# Motor_shield_2_0.net
KiCad netlist of a schematic drawn in EAGLE
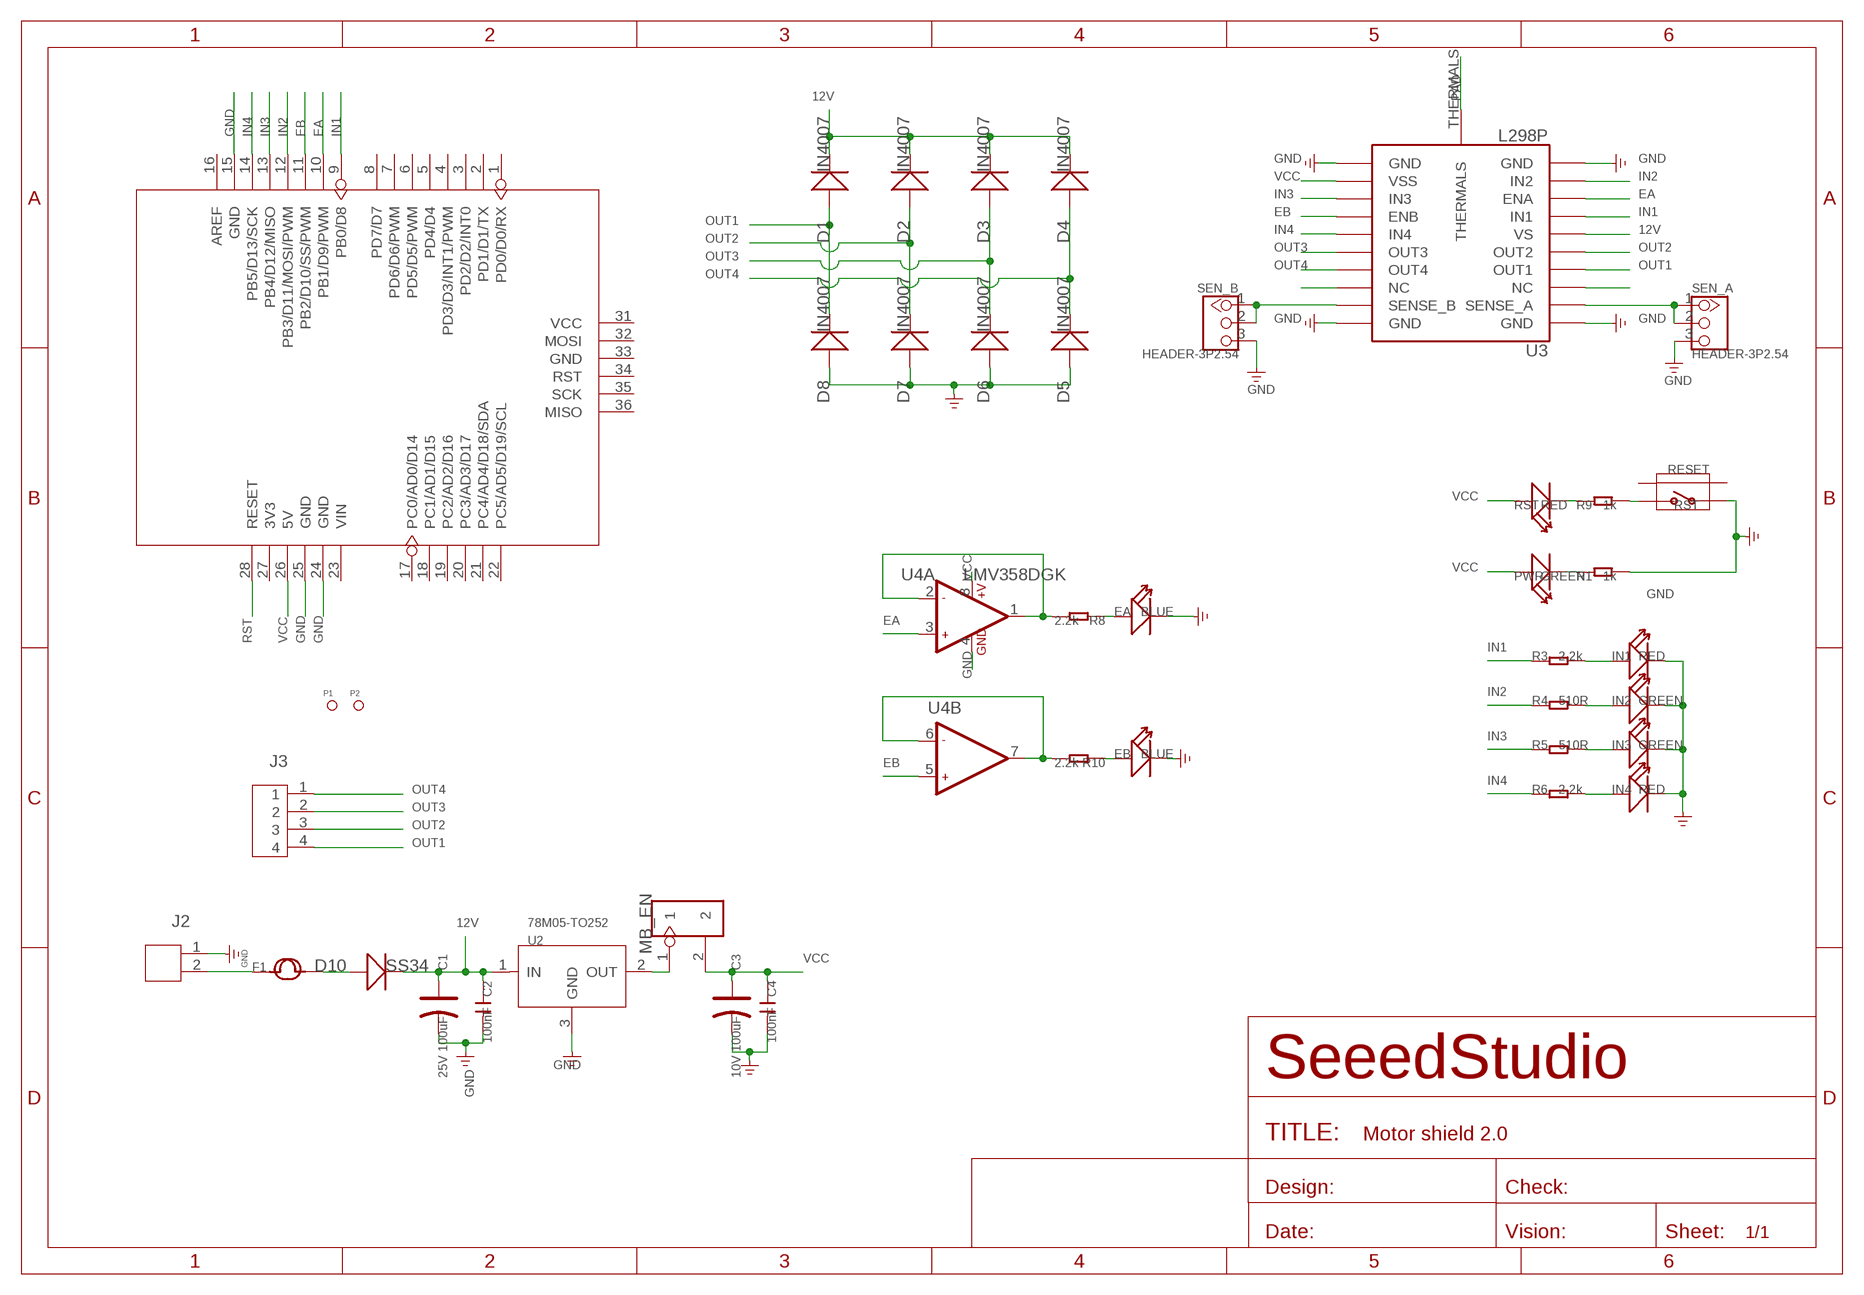
[diagram p0: schematic, sheet 1]

(export (version "E")
  (design (tool "Eeschema 10.0.6"))
  (components
    (comp (ref "C1")
      (value "25V 100uF")
      (footprint "eagle-import:ELECTRO-SMD-D-5.6MM")
      (libsource (lib "eagle-import") (part "CAP-ELECTRO-D"))
    )
    (comp (ref "C2")
      (value "100nF")
      (footprint "eagle-import:C0603")
      (libsource (lib "eagle-import") (part "C-0603"))
    )
    (comp (ref "C3")
      (value "10V 100uF")
      (footprint "eagle-import:AVX-B")
      (libsource (lib "eagle-import") (part "CAP-AVX-B"))
    )
    (comp (ref "C4")
      (value "100nF")
      (footprint "eagle-import:C0603")
      (libsource (lib "eagle-import") (part "C-0603"))
    )
    (comp (ref "D1")
      (value "IN4007")
      (footprint "eagle-import:D2010")
      (libsource (lib "eagle-import") (part "D'SMA'"))
    )
    (comp (ref "D2")
      (value "IN4007")
      (footprint "eagle-import:D2010")
      (libsource (lib "eagle-import") (part "D'SMA'"))
    )
    (comp (ref "D3")
      (value "IN4007")
      (footprint "eagle-import:D2010")
      (libsource (lib "eagle-import") (part "D'SMA'"))
    )
    (comp (ref "D4")
      (value "IN4007")
      (footprint "eagle-import:D2010")
      (libsource (lib "eagle-import") (part "D'SMA'"))
    )
    (comp (ref "D5")
      (value "IN4007")
      (footprint "eagle-import:D2010")
      (libsource (lib "eagle-import") (part "D'SMA'"))
    )
    (comp (ref "D6")
      (value "IN4007")
      (footprint "eagle-import:D2010")
      (libsource (lib "eagle-import") (part "D'SMA'"))
    )
    (comp (ref "D7")
      (value "IN4007")
      (footprint "eagle-import:D2010")
      (libsource (lib "eagle-import") (part "D'SMA'"))
    )
    (comp (ref "D8")
      (value "IN4007")
      (footprint "eagle-import:D2010")
      (libsource (lib "eagle-import") (part "D'SMA'"))
    )
    (comp (ref "D10")
      (value "SS34")
      (footprint "eagle-import:DO-214AB")
      (libsource (lib "eagle-import") (part "D'DO-214AB'"))
    )
    (comp (ref "EA")
      (value "BLUE")
      (footprint "eagle-import:D0603")
      (libsource (lib "eagle-import") (part "007-LED0603"))
    )
    (comp (ref "EB")
      (value "BLUE")
      (footprint "eagle-import:D0603")
      (libsource (lib "eagle-import") (part "007-LED0603"))
    )
    (comp (ref "F1")
      (value "FUSE'RLD30P250UF'")
      (footprint "eagle-import:0311")
      (libsource (lib "eagle-import") (part "FUSE'RLD30P250UF'"))
    )
    (comp (ref "IN1")
      (value "RED")
      (footprint "eagle-import:D0603")
      (libsource (lib "eagle-import") (part "007-LED0603"))
    )
    (comp (ref "IN2")
      (value "GREEN")
      (footprint "eagle-import:D0603")
      (libsource (lib "eagle-import") (part "007-LED0603"))
    )
    (comp (ref "IN3")
      (value "GREEN")
      (footprint "eagle-import:D0603")
      (libsource (lib "eagle-import") (part "007-LED0603"))
    )
    (comp (ref "IN4")
      (value "RED")
      (footprint "eagle-import:D0603")
      (libsource (lib "eagle-import") (part "007-LED0603"))
    )
    (comp (ref "J2")
      (value "JST-2P-LEADED'3.36'")
      (footprint "eagle-import:2P-3.36-LEADED-7X7")
      (libsource (lib "eagle-import") (part "JST-2P-LEADED'3.36'"))
    )
    (comp (ref "J3")
      (value "JST-4P-3.36-LEADED")
      (footprint "eagle-import:4P-3.36-LEADED-7X14")
      (libsource (lib "eagle-import") (part "JST-4P-3.36-LEADED"))
    )
    (comp (ref "MB_EN")
      (value "HEADER-2P-65/35MIL")
      (footprint "eagle-import:2P-2.54-65_35MIL")
      (libsource (lib "eagle-import") (part "HEADER-2P-65/35MIL"))
    )
    (comp (ref "P1")
      (value "PAD-MARK")
      (footprint "eagle-import:ROUND-MARK-1.0")
      (fields (field (name "PARTNO") "DNP"))
      (libsource (lib "eagle-import") (part "PAD-MARK"))
    )
    (comp (ref "P2")
      (value "PAD-MARK")
      (footprint "eagle-import:ROUND-MARK-1.0")
      (fields (field (name "PARTNO") "DNP"))
      (libsource (lib "eagle-import") (part "PAD-MARK"))
    )
    (comp (ref "PWR")
      (value "GREEN")
      (footprint "eagle-import:D0603")
      (libsource (lib "eagle-import") (part "007-LED0603"))
    )
    (comp (ref "R1")
      (value "1k")
      (footprint "eagle-import:R0603")
      (libsource (lib "eagle-import") (part "R-0603"))
    )
    (comp (ref "R3")
      (value "2.2k")
      (footprint "eagle-import:R0603")
      (libsource (lib "eagle-import") (part "R-0603"))
    )
    (comp (ref "R4")
      (value "510R")
      (footprint "eagle-import:R0603")
      (libsource (lib "eagle-import") (part "R-0603"))
    )
    (comp (ref "R5")
      (value "510R")
      (footprint "eagle-import:R0603")
      (libsource (lib "eagle-import") (part "R-0603"))
    )
    (comp (ref "R6")
      (value "2.2k")
      (footprint "eagle-import:R0603")
      (libsource (lib "eagle-import") (part "R-0603"))
    )
    (comp (ref "R8")
      (value "2.2k")
      (footprint "eagle-import:R0603")
      (libsource (lib "eagle-import") (part "R-0603"))
    )
    (comp (ref "R9")
      (value "1k")
      (footprint "eagle-import:R0603")
      (libsource (lib "eagle-import") (part "R-0603"))
    )
    (comp (ref "R10")
      (value "2.2k")
      (footprint "eagle-import:R0603")
      (libsource (lib "eagle-import") (part "R-0603"))
    )
    (comp (ref "RESET")
      (value "BUTTON-4P-REINFORCE'TS-118E'")
      (footprint "eagle-import:4P-SMD-7X3.5X3.5H")
      (libsource (lib "eagle-import") (part "BUTTON-4P-REINFORCE'TS-118E'"))
    )
    (comp (ref "RST")
      (value "RED")
      (footprint "eagle-import:D0603")
      (libsource (lib "eagle-import") (part "007-LED0603"))
    )
    (comp (ref "SEN_A")
      (value "HEADER-3P2.54")
      (footprint "eagle-import:2.54_1X3P")
      (libsource (lib "eagle-import") (part "HEADER-3P2.54"))
    )
    (comp (ref "SEN_B")
      (value "HEADER-3P2.54")
      (footprint "eagle-import:2.54_1X3P")
      (libsource (lib "eagle-import") (part "HEADER-3P2.54"))
    )
    (comp (ref "U1")
      (value "ARDUINO'W/-SILK")
      (footprint "eagle-import:ARDUINO")
      (libsource (lib "eagle-import") (part "ARDUINO'W/-SILK"))
    )
    (comp (ref "U2")
      (value "78M05-TO252")
      (footprint "eagle-import:TO252")
      (libsource (lib "eagle-import") (part "78M05-TO252"))
    )
    (comp (ref "U3")
      (value "L298P")
      (footprint "eagle-import:POWERSO-20")
      (libsource (lib "eagle-import") (part "L298P"))
    )
    (comp (ref "U4")
      (value "LMV358DGK")
      (footprint "eagle-import:MSOP8")
      (libsource (lib "eagle-import") (part "LMV358DGK"))
    )
  )
  (nets
    (net (code "1") (name "/12V") (class "Default")
      (node (ref "C1") (pin "+") (pinfunction "+_+") (pintype "passive"))
      (node (ref "C2") (pin "1") (pinfunction "1_1") (pintype "passive"))
      (node (ref "D1") (pin "-") (pinfunction "-_-") (pintype "passive"))
      (node (ref "D10") (pin "2") (pinfunction "-_2") (pintype "passive"))
      (node (ref "D2") (pin "-") (pinfunction "-_-") (pintype "passive"))
      (node (ref "D3") (pin "-") (pinfunction "-_-") (pintype "passive"))
      (node (ref "D4") (pin "-") (pinfunction "-_-") (pintype "passive"))
      (node (ref "U2") (pin "1") (pinfunction "IN_1") (pintype "bidirectional"))
      (node (ref "U3") (pin "P$6") (pinfunction "VS_P$6") (pintype "bidirectional"))
    )
    (net (code "2") (name "/EA") (class "Default")
      (node (ref "U1") (pin "10") (pinfunction "PB1/D9/PWM_10") (pintype "bidirectional"))
      (node (ref "U3") (pin "P$8") (pinfunction "ENA_P$8") (pintype "bidirectional"))
      (node (ref "U4") (pin "3") (pinfunction "+IN1_3") (pintype "input"))
    )
    (net (code "3") (name "/EB") (class "Default")
      (node (ref "U1") (pin "11") (pinfunction "PB2/D10/SS/PWM_11") (pintype "bidirectional"))
      (node (ref "U3") (pin "P$14") (pinfunction "ENB_P$14") (pintype "bidirectional"))
      (node (ref "U4") (pin "5") (pinfunction "+IN2_5") (pintype "input"))
    )
    (net (code "4") (name "/IN1") (class "Default")
      (node (ref "R3") (pin "1") (pinfunction "1_1") (pintype "passive"))
      (node (ref "U1") (pin "9") (pinfunction "PB0/D8_9") (pintype "bidirectional"))
      (node (ref "U3") (pin "P$7") (pinfunction "IN1_P$7") (pintype "bidirectional"))
    )
    (net (code "5") (name "/IN2") (class "Default")
      (node (ref "R4") (pin "1") (pinfunction "1_1") (pintype "passive"))
      (node (ref "U1") (pin "12") (pinfunction "PB3/D11/MOSI/PWM_12") (pintype "bidirectional"))
      (node (ref "U3") (pin "P$9") (pinfunction "IN2_P$9") (pintype "bidirectional"))
    )
    (net (code "6") (name "/IN3") (class "Default")
      (node (ref "R5") (pin "1") (pinfunction "1_1") (pintype "passive"))
      (node (ref "U1") (pin "13") (pinfunction "PB4/D12/MISO_13") (pintype "bidirectional"))
      (node (ref "U3") (pin "P$13") (pinfunction "IN3_P$13") (pintype "bidirectional"))
    )
    (net (code "7") (name "/IN4") (class "Default")
      (node (ref "R6") (pin "1") (pinfunction "1_1") (pintype "passive"))
      (node (ref "U1") (pin "14") (pinfunction "PB5/D13/SCK_14") (pintype "bidirectional"))
      (node (ref "U3") (pin "P$15") (pinfunction "IN4_P$15") (pintype "bidirectional"))
    )
    (net (code "8") (name "/OUT1") (class "Default")
      (node (ref "D1") (pin "+") (pinfunction "+_+") (pintype "passive"))
      (node (ref "D8") (pin "-") (pinfunction "-_-") (pintype "passive"))
      (node (ref "J3") (pin "4") (pinfunction "4_4") (pintype "bidirectional"))
      (node (ref "U3") (pin "P$4") (pinfunction "OUT1_P$4") (pintype "bidirectional"))
    )
    (net (code "9") (name "/OUT2") (class "Default")
      (node (ref "D2") (pin "+") (pinfunction "+_+") (pintype "passive"))
      (node (ref "D7") (pin "-") (pinfunction "-_-") (pintype "passive"))
      (node (ref "J3") (pin "3") (pinfunction "3_3") (pintype "bidirectional"))
      (node (ref "U3") (pin "P$5") (pinfunction "OUT2_P$5") (pintype "bidirectional"))
    )
    (net (code "10") (name "/OUT3") (class "Default")
      (node (ref "D3") (pin "+") (pinfunction "+_+") (pintype "passive"))
      (node (ref "D6") (pin "-") (pinfunction "-_-") (pintype "passive"))
      (node (ref "J3") (pin "2") (pinfunction "2_2") (pintype "bidirectional"))
      (node (ref "U3") (pin "P$16") (pinfunction "OUT3_P$16") (pintype "bidirectional"))
    )
    (net (code "11") (name "/OUT4") (class "Default")
      (node (ref "D4") (pin "+") (pinfunction "+_+") (pintype "passive"))
      (node (ref "D5") (pin "-") (pinfunction "-_-") (pintype "passive"))
      (node (ref "J3") (pin "1") (pinfunction "1_1") (pintype "bidirectional"))
      (node (ref "U3") (pin "P$17") (pinfunction "OUT4_P$17") (pintype "bidirectional"))
    )
    (net (code "12") (name "/PAD") (class "Default")
      (node (ref "U3") (pin "THERMALS") (pinfunction "THERMALS_THERMALS") (pintype "bidirectional"))
    )
    (net (code "13") (name "/RST") (class "Default")
      (node (ref "R9") (pin "2") (pinfunction "2_2") (pintype "passive"))
      (node (ref "RESET") (pin "2") (pinfunction "2_2") (pintype "bidirectional"))
      (node (ref "U1") (pin "28") (pinfunction "RESET_28") (pintype "bidirectional"))
    )
    (net (code "14") (name "/VCC") (class "Default")
      (node (ref "C3") (pin "+") (pinfunction "+_+") (pintype "passive"))
      (node (ref "C4") (pin "1") (pinfunction "1_1") (pintype "passive"))
      (node (ref "MB_EN") (pin "2") (pinfunction "2_2") (pintype "bidirectional"))
      (node (ref "PWR") (pin "+") (pinfunction "+_+") (pintype "passive"))
      (node (ref "RST") (pin "+") (pinfunction "+_+") (pintype "passive"))
      (node (ref "U1") (pin "26") (pinfunction "5V_26") (pintype "bidirectional"))
      (node (ref "U3") (pin "P$12") (pinfunction "VSS_P$12") (pintype "bidirectional"))
      (node (ref "U4") (pin "8") (pinfunction "+V_8") (pintype "power_in"))
    )
    (net (code "15") (name "GND") (class "Default")
      (node (ref "C1") (pin "-") (pinfunction "-_-") (pintype "passive"))
      (node (ref "C2") (pin "2") (pinfunction "2_2") (pintype "passive"))
      (node (ref "C3") (pin "-") (pinfunction "-_-") (pintype "passive"))
      (node (ref "C4") (pin "2") (pinfunction "2_2") (pintype "passive"))
      (node (ref "D5") (pin "+") (pinfunction "+_+") (pintype "passive"))
      (node (ref "D6") (pin "+") (pinfunction "+_+") (pintype "passive"))
      (node (ref "D7") (pin "+") (pinfunction "+_+") (pintype "passive"))
      (node (ref "D8") (pin "+") (pinfunction "+_+") (pintype "passive"))
      (node (ref "EA") (pin "-") (pinfunction "-_-") (pintype "passive"))
      (node (ref "EB") (pin "-") (pinfunction "-_-") (pintype "passive"))
      (node (ref "IN1") (pin "-") (pinfunction "-_-") (pintype "passive"))
      (node (ref "IN2") (pin "-") (pinfunction "-_-") (pintype "passive"))
      (node (ref "IN3") (pin "-") (pinfunction "-_-") (pintype "passive"))
      (node (ref "IN4") (pin "-") (pinfunction "-_-") (pintype "passive"))
      (node (ref "J2") (pin "1") (pinfunction "P$1_1") (pintype "bidirectional"))
      (node (ref "R1") (pin "2") (pinfunction "2_2") (pintype "passive"))
      (node (ref "RESET") (pin "1") (pinfunction "1_1") (pintype "bidirectional"))
      (node (ref "SEN_A") (pin "3") (pinfunction "P$3_3") (pintype "bidirectional"))
      (node (ref "SEN_B") (pin "3") (pinfunction "P$3_3") (pintype "bidirectional"))
      (node (ref "U1") (pin "15") (pinfunction "GND_15") (pintype "bidirectional"))
      (node (ref "U1") (pin "24") (pinfunction "GND_24") (pintype "bidirectional"))
      (node (ref "U1") (pin "25") (pinfunction "GND_25") (pintype "bidirectional"))
      (node (ref "U2") (pin "3") (pinfunction "GND_3") (pintype "bidirectional"))
      (node (ref "U3") (pin "P$1") (pinfunction "GND_P$1") (pintype "bidirectional"))
      (node (ref "U3") (pin "P$10") (pinfunction "GND_P$10") (pintype "bidirectional"))
      (node (ref "U3") (pin "P$11") (pinfunction "GND_P$11") (pintype "bidirectional"))
      (node (ref "U3") (pin "P$20") (pinfunction "GND_P$20") (pintype "bidirectional"))
      (node (ref "U4") (pin "4") (pinfunction "GND_4") (pintype "power_in"))
    )
    (net (code "16") (name "Net-(D10-+)") (class "Default")
      (node (ref "D10") (pin "1") (pinfunction "+_1") (pintype "passive"))
      (node (ref "F1") (pin "2") (pinfunction "2_2") (pintype "bidirectional"))
    )
    (net (code "17") (name "Net-(EA-Pad+)") (class "Default")
      (node (ref "EA") (pin "+") (pinfunction "+_+") (pintype "passive"))
      (node (ref "R8") (pin "1") (pinfunction "1_1") (pintype "passive"))
    )
    (net (code "18") (name "Net-(EB-Pad+)") (class "Default")
      (node (ref "EB") (pin "+") (pinfunction "+_+") (pintype "passive"))
      (node (ref "R10") (pin "1") (pinfunction "1_1") (pintype "passive"))
    )
    (net (code "19") (name "Net-(IN1-Pad+)") (class "Default")
      (node (ref "IN1") (pin "+") (pinfunction "+_+") (pintype "passive"))
      (node (ref "R3") (pin "2") (pinfunction "2_2") (pintype "passive"))
    )
    (net (code "20") (name "Net-(IN2-Pad+)") (class "Default")
      (node (ref "IN2") (pin "+") (pinfunction "+_+") (pintype "passive"))
      (node (ref "R4") (pin "2") (pinfunction "2_2") (pintype "passive"))
    )
    (net (code "21") (name "Net-(IN3-Pad+)") (class "Default")
      (node (ref "IN3") (pin "+") (pinfunction "+_+") (pintype "passive"))
      (node (ref "R5") (pin "2") (pinfunction "2_2") (pintype "passive"))
    )
    (net (code "22") (name "Net-(IN4-Pad+)") (class "Default")
      (node (ref "IN4") (pin "+") (pinfunction "+_+") (pintype "passive"))
      (node (ref "R6") (pin "2") (pinfunction "2_2") (pintype "passive"))
    )
    (net (code "23") (name "Net-(J2-P$2)") (class "Default")
      (node (ref "F1") (pin "1") (pinfunction "1_1") (pintype "bidirectional"))
      (node (ref "J2") (pin "2") (pinfunction "P$2_2") (pintype "bidirectional"))
    )
    (net (code "24") (name "Net-(PWR-Pad-)") (class "Default")
      (node (ref "PWR") (pin "-") (pinfunction "-_-") (pintype "passive"))
      (node (ref "R1") (pin "1") (pinfunction "1_1") (pintype "passive"))
    )
    (net (code "25") (name "Net-(R9-Pad1)") (class "Default")
      (node (ref "R9") (pin "1") (pinfunction "1_1") (pintype "passive"))
      (node (ref "RST") (pin "-") (pinfunction "-_-") (pintype "passive"))
    )
    (net (code "26") (name "Net-(SEN_A-P$1)") (class "Default")
      (node (ref "SEN_A") (pin "1") (pinfunction "P$1_1") (pintype "bidirectional"))
      (node (ref "SEN_A") (pin "2") (pinfunction "P$2_2") (pintype "bidirectional"))
      (node (ref "U3") (pin "P$2") (pinfunction "SENSE_A_P$2") (pintype "bidirectional"))
    )
    (net (code "27") (name "Net-(SEN_B-P$1)") (class "Default")
      (node (ref "SEN_B") (pin "1") (pinfunction "P$1_1") (pintype "bidirectional"))
      (node (ref "SEN_B") (pin "2") (pinfunction "P$2_2") (pintype "bidirectional"))
      (node (ref "U3") (pin "P$19") (pinfunction "SENSE_B_P$19") (pintype "bidirectional"))
    )
    (net (code "28") (name "Net-(U2-OUT)") (class "Default")
      (node (ref "MB_EN") (pin "1") (pinfunction "1_1") (pintype "bidirectional"))
      (node (ref "U2") (pin "2") (pinfunction "OUT_2") (pintype "bidirectional"))
    )
    (net (code "29") (name "Net-(U4A--IN1)") (class "Default")
      (node (ref "R8") (pin "2") (pinfunction "2_2") (pintype "passive"))
      (node (ref "U4") (pin "1") (pinfunction "OUT1_1") (pintype "output"))
      (node (ref "U4") (pin "2") (pinfunction "-IN1_2") (pintype "input"))
    )
    (net (code "30") (name "Net-(U4B--IN2)") (class "Default")
      (node (ref "R10") (pin "2") (pinfunction "2_2") (pintype "passive"))
      (node (ref "U4") (pin "6") (pinfunction "-IN2_6") (pintype "input"))
      (node (ref "U4") (pin "7") (pinfunction "OUT2_7") (pintype "output"))
    )
    (net (code "31") (name "unconnected-(RESET-PadS1)") (class "Default")
      (node (ref "RESET") (pin "S1") (pinfunction "S1_S1") (pintype "bidirectional"))
    )
    (net (code "32") (name "unconnected-(RESET-PadS2)") (class "Default")
      (node (ref "RESET") (pin "S2") (pinfunction "S2_S2") (pintype "bidirectional"))
    )
    (net (code "33") (name "unconnected-(U1-3V3-Pad27)") (class "Default")
      (node (ref "U1") (pin "27") (pinfunction "3V3_27") (pintype "bidirectional"))
    )
    (net (code "34") (name "unconnected-(U1-AREF-Pad16)") (class "Default")
      (node (ref "U1") (pin "16") (pinfunction "AREF_16") (pintype "bidirectional"))
    )
    (net (code "35") (name "unconnected-(U1-GND-Pad33)") (class "Default")
      (node (ref "U1") (pin "33") (pinfunction "GND_33") (pintype "bidirectional"))
    )
    (net (code "36") (name "unconnected-(U1-MISO-Pad36)") (class "Default")
      (node (ref "U1") (pin "36") (pinfunction "MISO_36") (pintype "bidirectional"))
    )
    (net (code "37") (name "unconnected-(U1-MOSI-Pad32)") (class "Default")
      (node (ref "U1") (pin "32") (pinfunction "MOSI_32") (pintype "bidirectional"))
    )
    (net (code "38") (name "unconnected-(U1-PC0{slash}AD0{slash}D14-Pad17)") (class "Default")
      (node (ref "U1") (pin "17") (pinfunction "PC0/AD0/D14_17") (pintype "bidirectional"))
    )
    (net (code "39") (name "unconnected-(U1-PC1{slash}AD1{slash}D15-Pad18)") (class "Default")
      (node (ref "U1") (pin "18") (pinfunction "PC1/AD1/D15_18") (pintype "bidirectional"))
    )
    (net (code "40") (name "unconnected-(U1-PC2{slash}AD2{slash}D16-Pad19)") (class "Default")
      (node (ref "U1") (pin "19") (pinfunction "PC2/AD2/D16_19") (pintype "bidirectional"))
    )
    (net (code "41") (name "unconnected-(U1-PC3{slash}AD3{slash}D17-Pad20)") (class "Default")
      (node (ref "U1") (pin "20") (pinfunction "PC3/AD3/D17_20") (pintype "bidirectional"))
    )
    (net (code "42") (name "unconnected-(U1-PC4{slash}AD4{slash}D18{slash}SDA-Pad21)") (class "Default")
      (node (ref "U1") (pin "21") (pinfunction "PC4/AD4/D18/SDA_21") (pintype "bidirectional"))
    )
    (net (code "43") (name "unconnected-(U1-PC5{slash}AD5{slash}D19{slash}SCL-Pad22)") (class "Default")
      (node (ref "U1") (pin "22") (pinfunction "PC5/AD5/D19/SCL_22") (pintype "bidirectional"))
    )
    (net (code "44") (name "unconnected-(U1-PD0{slash}D0{slash}RX-Pad1)") (class "Default")
      (node (ref "U1") (pin "1") (pinfunction "PD0/D0/RX_1") (pintype "bidirectional"))
    )
    (net (code "45") (name "unconnected-(U1-PD1{slash}D1{slash}TX-Pad2)") (class "Default")
      (node (ref "U1") (pin "2") (pinfunction "PD1/D1/TX_2") (pintype "bidirectional"))
    )
    (net (code "46") (name "unconnected-(U1-PD2{slash}D2{slash}INT0-Pad3)") (class "Default")
      (node (ref "U1") (pin "3") (pinfunction "PD2/D2/INT0_3") (pintype "bidirectional"))
    )
    (net (code "47") (name "unconnected-(U1-PD3{slash}D3{slash}INT1{slash}PWM-Pad4)") (class "Default")
      (node (ref "U1") (pin "4") (pinfunction "PD3/D3/INT1/PWM_4") (pintype "bidirectional"))
    )
    (net (code "48") (name "unconnected-(U1-PD4{slash}D4-Pad5)") (class "Default")
      (node (ref "U1") (pin "5") (pinfunction "PD4/D4_5") (pintype "bidirectional"))
    )
    (net (code "49") (name "unconnected-(U1-PD5{slash}D5{slash}PWM-Pad6)") (class "Default")
      (node (ref "U1") (pin "6") (pinfunction "PD5/D5/PWM_6") (pintype "bidirectional"))
    )
    (net (code "50") (name "unconnected-(U1-PD6{slash}D6{slash}PWM-Pad7)") (class "Default")
      (node (ref "U1") (pin "7") (pinfunction "PD6/D6/PWM_7") (pintype "bidirectional"))
    )
    (net (code "51") (name "unconnected-(U1-PD7{slash}D7-Pad8)") (class "Default")
      (node (ref "U1") (pin "8") (pinfunction "PD7/D7_8") (pintype "bidirectional"))
    )
    (net (code "52") (name "unconnected-(U1-RST-Pad34)") (class "Default")
      (node (ref "U1") (pin "34") (pinfunction "RST_34") (pintype "bidirectional"))
    )
    (net (code "53") (name "unconnected-(U1-SCK-Pad35)") (class "Default")
      (node (ref "U1") (pin "35") (pinfunction "SCK_35") (pintype "bidirectional"))
    )
    (net (code "54") (name "unconnected-(U1-VCC-Pad31)") (class "Default")
      (node (ref "U1") (pin "31") (pinfunction "VCC_31") (pintype "bidirectional"))
    )
    (net (code "55") (name "unconnected-(U1-VIN-Pad23)") (class "Default")
      (node (ref "U1") (pin "23") (pinfunction "VIN_23") (pintype "bidirectional"))
    )
    (net (code "56") (name "unconnected-(U3-NC-PadP$3)") (class "Default")
      (node (ref "U3") (pin "P$3") (pinfunction "NC_P$3") (pintype "bidirectional"))
    )
    (net (code "57") (name "unconnected-(U3-NC-PadP$18)") (class "Default")
      (node (ref "U3") (pin "P$18") (pinfunction "NC_P$18") (pintype "bidirectional"))
    )
  )
)
